# DIOT_Connectors.net
KiCad netlist of a schematic drawn in Altium Designer
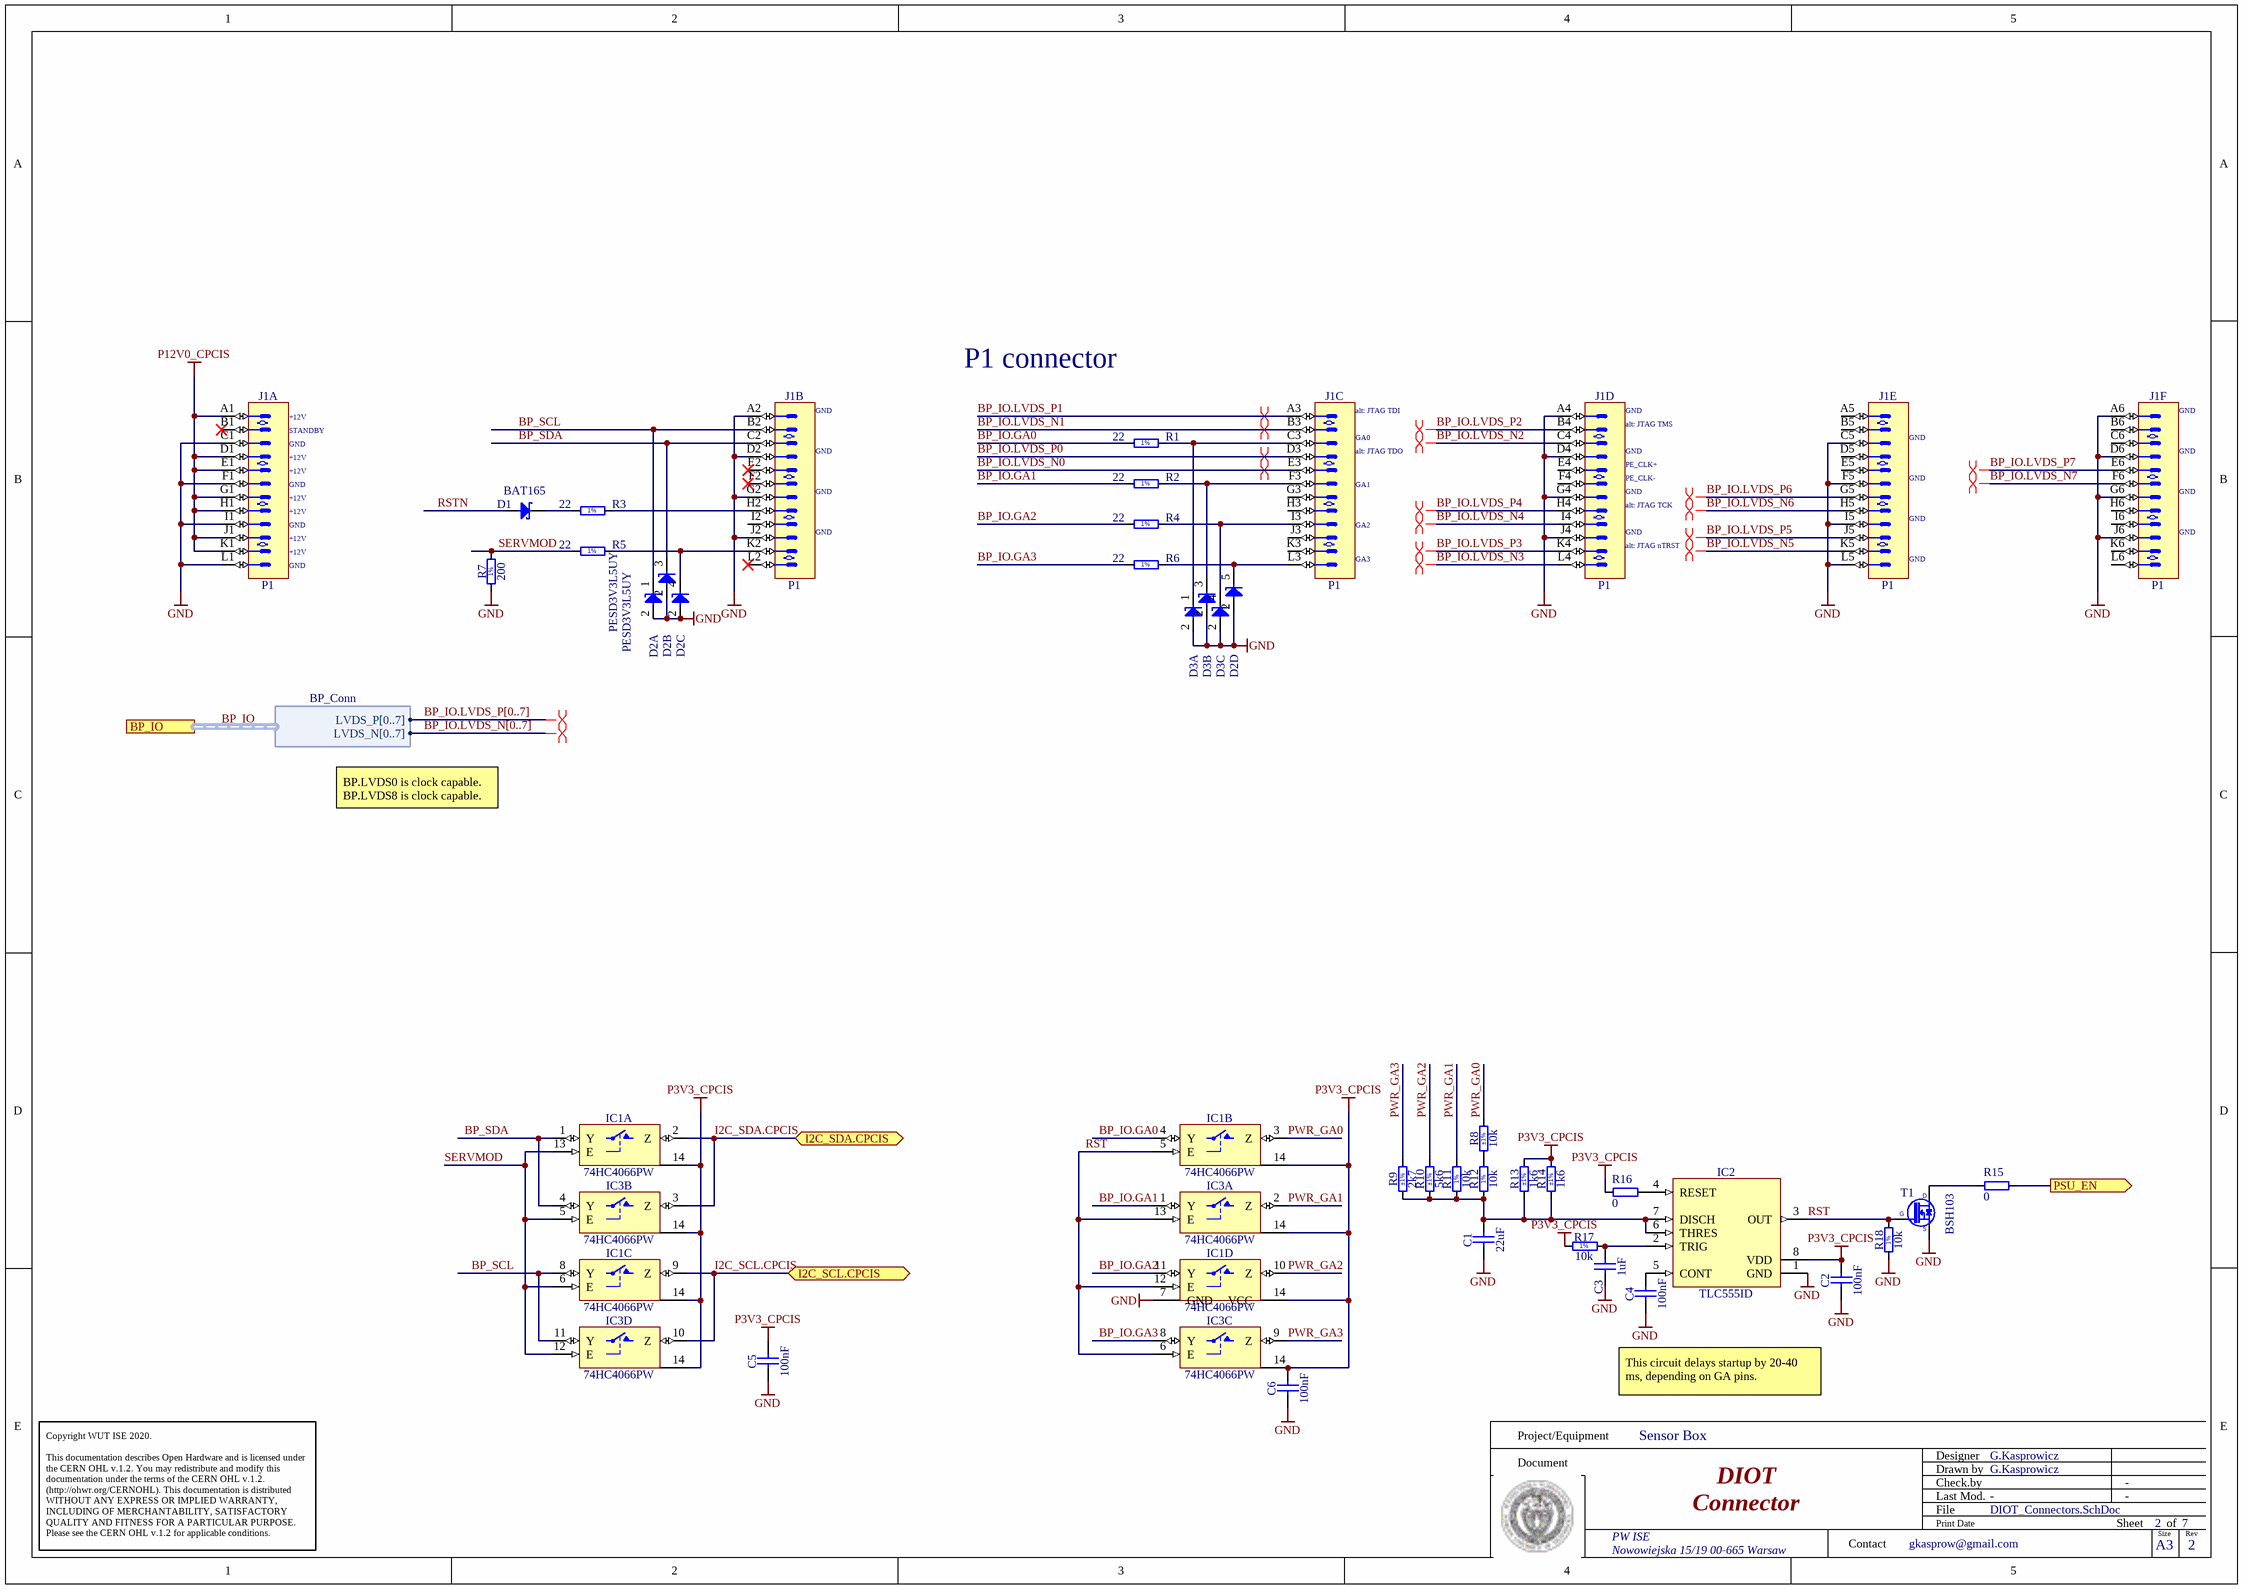
[diagram p0: DIOT_Connectors.SchDoc]

(export (version "E")
  (design (tool "Eeschema 10.0.6"))
  (components
    (comp (ref "C1")
      (value "22uF")
      (footprint "CAPC1608X90N")
      (description "Non-polarised capacitor")
      (fields
        (field (name "MANUFACTURER") "GENERIC")
        (field (name "PART NUMBER") "CC0603_22UF_6.3V_20%_X5R")
        (field (name "AUTHOR") "CERN DEM JLC")
      )
      (libsource (lib "Capacitors") (part "Capacitor - non polarized"))
    )
    (comp (ref "C2")
      (value "100nF")
      (footprint "CAPC1005X55N")
      (description "Non-polarised capacitor")
      (fields
        (field (name "PART NUMBER") "CC0402_100NF_16V_10%_X5R")
        (field (name "VOLTAGE") "16V")
        (field (name "AUTHOR") "CERN DEM JLC")
      )
      (libsource (lib "Capacitors") (part "Capacitor - non polarized"))
    )
    (comp (ref "C3")
      (value "1uF")
      (footprint "CAPC1005X55N")
      (description "Non-polarised capacitor")
      (fields
        (field (name "PART NUMBER") "CC0402_1UF_16V_10%_X5R")
        (field (name "VOLTAGE") "16V")
        (field (name "AUTHOR") "CERN DEM JLC")
      )
      (libsource (lib "Capacitors") (part "Capacitor - non polarized"))
    )
    (comp (ref "C4")
      (value "100nF")
      (footprint "CAPC1005X55N")
      (description "Non-polarised capacitor")
      (fields
        (field (name "PART NUMBER") "CC0402_100NF_16V_10%_X5R")
        (field (name "VOLTAGE") "16V")
        (field (name "AUTHOR") "CERN DEM JLC")
      )
      (libsource (lib "Capacitors") (part "Capacitor - non polarized"))
    )
    (comp (ref "C5")
      (value "100nF")
      (footprint "CAPC1005X55N")
      (description "Non-polarised capacitor")
      (fields
        (field (name "PART NUMBER") "CC0402_100NF_16V_10%_X5R")
        (field (name "VOLTAGE") "16V")
        (field (name "AUTHOR") "CERN DEM JLC")
      )
      (libsource (lib "Capacitors") (part "Capacitor - non polarized"))
    )
    (comp (ref "C6")
      (value "100nF")
      (footprint "CAPC1005X55N")
      (description "Non-polarised capacitor")
      (fields
        (field (name "PART NUMBER") "CC0402_100NF_16V_10%_X5R")
        (field (name "VOLTAGE") "16V")
        (field (name "AUTHOR") "CERN DEM JLC")
      )
      (libsource (lib "Capacitors") (part "Capacitor - non polarized"))
    )
    (comp (ref "D1")
      (value "BAT165")
      (footprint "SOD2512X110N")
      (description "Schottky Diode")
      (fields
        (field (name "MANUFACTURER") "INFINEON")
        (field (name "VOLTAGE") "40V")
        (field (name "AUTHOR") "CERN DEM JLC")
      )
      (libsource (lib "ICs And Semiconductors") (part "Diode Schottky"))
    )
    (comp (ref "D2")
      (value "PESD3V3L5UY")
      (footprint "SOT65P210X110-6N")
      (description "Fivefold ESD Protection Diode Arrays")
      (fields
        (field (name "VOLTAGE") "3.3V")
        (field (name "POWER") "200W")
        (field (name "AUTHOR") "CERN DEM WB")
      )
      (libsource (lib "ICs And Semiconductors") (part "PESD Array 5diodes 6pins Common anode2"))
    )
    (comp (ref "D3")
      (value "PESD3V3L5UY")
      (footprint "SOT65P210X110-6N")
      (description "Fivefold ESD Protection Diode Arrays")
      (fields
        (field (name "VOLTAGE") "3.3V")
        (field (name "POWER") "200W")
        (field (name "AUTHOR") "CERN DEM WB")
      )
      (libsource (lib "ICs And Semiconductors") (part "PESD Array 5diodes 6pins Common anode2"))
    )
    (comp (ref "IC1")
      (value "74HC4066PW")
      (footprint "SOP65P640X110-14N")
      (fields (field (name "MANUFACTURER") "NXP SEMICONDUCTORS") (field (name "AUTHOR") "CERN DEM JLC"))
      (libsource (lib "ICs And Semiconductors") (part "4066"))
    )
    (comp (ref "IC2")
      (value "TLC555ID")
      (footprint "SOIC127P600X175-8N")
      (description "LinCMOS Timer")
      (fields (field (name "MANUFACTURER") "TEXAS INSTRUMENTS") (field (name "AUTHOR") "CERN DEM JMW"))
      (libsource (lib "ICs And Semiconductors") (part "TLC555"))
    )
    (comp (ref "IC3")
      (value "74HC4066PW")
      (footprint "SOP65P640X110-14N")
      (fields (field (name "MANUFACTURER") "NXP SEMICONDUCTORS") (field (name "AUTHOR") "CERN DEM JLC"))
      (libsource (lib "ICs And Semiconductors") (part "4066"))
    )
    (comp (ref "J1")
      (value "P1")
      (footprint "AMPHENOL_10052825-101LF")
      (description "72 Contacts Header, 6 Columns, 4 Pairs per Column")
      (fields
        (field (name "PART NUMBER") "AMPHENOL_10052825-101LF")
        (field (name "MANUFACTURER") "AMPHENOL")
        (field (name "AUTHOR") "CERN DEM MR")
      )
      (libsource (lib "Connectors") (part "AMPHENOL_10052825-101LF"))
    )
    (comp (ref "R1")
      (value "22")
      (footprint "RESC1005X40N")
      (description "Resistor - 1%")
      (fields
        (field (name "PART NUMBER") "R0402_22R_1%_0.0625W_100PPM")
        (field (name "POWER") "0.0625W")
        (field (name "AUTHOR") "CERN DEM JLC")
      )
      (libsource (lib "Resistors") (part "Resistor - 1%"))
    )
    (comp (ref "R2")
      (value "22")
      (footprint "RESC1005X40N")
      (description "Resistor - 1%")
      (fields
        (field (name "PART NUMBER") "R0402_22R_1%_0.0625W_100PPM")
        (field (name "POWER") "0.0625W")
        (field (name "AUTHOR") "CERN DEM JLC")
      )
      (libsource (lib "Resistors") (part "Resistor - 1%"))
    )
    (comp (ref "R3")
      (value "22")
      (footprint "RESC1005X40N")
      (description "Resistor - 1%")
      (fields
        (field (name "PART NUMBER") "R0402_22R_1%_0.0625W_100PPM")
        (field (name "POWER") "0.0625W")
        (field (name "AUTHOR") "CERN DEM JLC")
      )
      (libsource (lib "Resistors") (part "Resistor - 1%"))
    )
    (comp (ref "R4")
      (value "22")
      (footprint "RESC1005X40N")
      (description "Resistor - 1%")
      (fields
        (field (name "PART NUMBER") "R0402_22R_1%_0.0625W_100PPM")
        (field (name "POWER") "0.0625W")
        (field (name "AUTHOR") "CERN DEM JLC")
      )
      (libsource (lib "Resistors") (part "Resistor - 1%"))
    )
    (comp (ref "R5")
      (value "22")
      (footprint "RESC1005X40N")
      (description "Resistor - 1%")
      (fields
        (field (name "PART NUMBER") "R0402_22R_1%_0.0625W_100PPM")
        (field (name "POWER") "0.0625W")
        (field (name "AUTHOR") "CERN DEM JLC")
      )
      (libsource (lib "Resistors") (part "Resistor - 1%"))
    )
    (comp (ref "R6")
      (value "22")
      (footprint "RESC1005X40N")
      (description "Resistor - 1%")
      (fields
        (field (name "PART NUMBER") "R0402_22R_1%_0.0625W_100PPM")
        (field (name "POWER") "0.0625W")
        (field (name "AUTHOR") "CERN DEM JLC")
      )
      (libsource (lib "Resistors") (part "Resistor - 1%"))
    )
    (comp (ref "R7")
      (value "200")
      (footprint "RESC1005X40N")
      (description "Resistor - 1%")
      (fields
        (field (name "PART NUMBER") "R0402_200R_1%_0.0625W_100PPM")
        (field (name "POWER") "0.0625W")
        (field (name "AUTHOR") "CERN DEM JLC")
      )
      (libsource (lib "Resistors") (part "Resistor - 1%"))
    )
    (comp (ref "R8")
      (value "10k")
      (footprint "RESC1005X40N")
      (description "Resistor - 1%")
      (fields
        (field (name "PART NUMBER") "R0402_10K_1%_0.0625W_100PPM")
        (field (name "POWER") "0.0625W")
        (field (name "TOLERANCE") "±1%")
        (field (name "AUTHOR") "CERN DEM JLC")
      )
      (libsource (lib "Resistors") (part "Resistor - 1%"))
    )
    (comp (ref "R9")
      (value "2k7")
      (footprint "RESC1608X55N")
      (description "Resistor - 1%")
      (fields
        (field (name "PART NUMBER") "R0603_2K7_1%_0.1W_100PPM")
        (field (name "POWER") "0.1W")
        (field (name "TOLERANCE") "±1%")
        (field (name "AUTHOR") "CERN DEM JLC")
      )
      (libsource (lib "Resistors") (part "Resistor - 1%"))
    )
    (comp (ref "R10")
      (value "5k6")
      (footprint "RESC1005X40N")
      (description "Resistor - 1%")
      (fields
        (field (name "PART NUMBER") "R0402_5K6_1%_0.0625W_100PPM")
        (field (name "POWER") "0.0625W")
        (field (name "TOLERANCE") "±1%")
        (field (name "AUTHOR") "CERN DEM JLC")
      )
      (libsource (lib "Resistors") (part "Resistor - 1%"))
    )
    (comp (ref "R11")
      (value "10k")
      (footprint "RESC1005X40N")
      (description "Resistor - 1%")
      (fields
        (field (name "PART NUMBER") "R0402_1K_1%_0.0625W_100PPM")
        (field (name "POWER") "0.0625W")
        (field (name "AUTHOR") "CERN DEM JLC")
      )
      (libsource (lib "Resistors") (part "Resistor - 1%"))
    )
    (comp (ref "R12")
      (value "10k")
      (footprint "RESC1005X40N")
      (description "Resistor - 1%")
      (fields
        (field (name "PART NUMBER") "R0402_1K_1%_0.0625W_100PPM")
        (field (name "POWER") "0.0625W")
        (field (name "AUTHOR") "CERN DEM JLC")
      )
      (libsource (lib "Resistors") (part "Resistor - 1%"))
    )
    (comp (ref "R13")
      (value "1k6")
      (footprint "RESC1005X40N")
      (description "Resistor - 1%")
      (fields
        (field (name "PART NUMBER") "R0402_1K6_1%_0.0625W_100PPM")
        (field (name "POWER") "0.0625W")
        (field (name "TOLERANCE") "±1%")
        (field (name "AUTHOR") "CERN DEM JLC")
      )
      (libsource (lib "Resistors") (part "Resistor - 1%"))
    )
    (comp (ref "R14")
      (value "1k6")
      (footprint "RESC1005X40N")
      (description "Resistor - 1%")
      (fields
        (field (name "PART NUMBER") "R0402_1K6_1%_0.0625W_100PPM")
        (field (name "POWER") "0.0625W")
        (field (name "TOLERANCE") "±1%")
        (field (name "AUTHOR") "CERN DEM JLC")
      )
      (libsource (lib "Resistors") (part "Resistor - 1%"))
    )
    (comp (ref "R15")
      (value "0")
      (footprint "RESC1005X40N")
      (description "Resistor")
      (fields
        (field (name "PART NUMBER") "R0402_0R_JUMPER")
        (field (name "MANUFACTURER") "GENERIC")
        (field (name "AUTHOR") "CERN DEM JLC")
      )
      (libsource (lib "Resistors") (part "Resistor"))
    )
    (comp (ref "R16")
      (value "0")
      (footprint "RESC1005X40N")
      (description "Resistor")
      (fields
        (field (name "PART NUMBER") "R0402_0R_JUMPER")
        (field (name "MANUFACTURER") "GENERIC")
        (field (name "AUTHOR") "CERN DEM JLC")
      )
      (libsource (lib "Resistors") (part "Resistor"))
    )
    (comp (ref "R17")
      (value "10k")
      (footprint "RESC1005X40N")
      (description "Resistor - 1%")
      (fields
        (field (name "PART NUMBER") "R0402_10K_1%_0.0625W_100PPM")
        (field (name "POWER") "0.0625W")
        (field (name "AUTHOR") "CERN DEM JLC")
      )
      (libsource (lib "Resistors") (part "Resistor - 1%"))
    )
    (comp (ref "R18")
      (value "10k")
      (footprint "RESC1005X40N")
      (description "Resistor - 1%")
      (fields
        (field (name "PART NUMBER") "R0402_10K_1%_0.0625W_100PPM")
        (field (name "POWER") "0.0625W")
        (field (name "AUTHOR") "CERN DEM JLC")
      )
      (libsource (lib "Resistors") (part "Resistor - 1%"))
    )
    (comp (ref "T1")
      (value "BSH103")
      (footprint "SOT95P230X110-3N")
      (description "N-CHANNEL MOSFET WITH DIODE")
      (fields (field (name "MANUFACTURER") "NEXPERIA") (field (name "AUTHOR") "CERN DEM JLC"))
      (libsource (lib "ICs And Semiconductors") (part "N-MOSFET-D 1G 2S 3D"))
    )
  )
  (nets
    (net (code "2") (name "/BP_IO.GA0") (class "Default")
      (node (ref "IC1") (pin "4") (pinfunction "Y_4") (pintype "bidirectional"))
      (node (ref "R1") (pin "1") (pinfunction "1_1") (pintype "passive"))
    )
    (net (code "3") (name "/BP_IO.GA1") (class "Default")
      (node (ref "IC3") (pin "1") (pinfunction "Y_1") (pintype "bidirectional"))
      (node (ref "R2") (pin "1") (pinfunction "1_1") (pintype "passive"))
    )
    (net (code "4") (name "/BP_IO.GA2") (class "Default")
      (node (ref "IC1") (pin "11") (pinfunction "Y_11") (pintype "bidirectional"))
      (node (ref "R4") (pin "1") (pinfunction "1_1") (pintype "passive"))
    )
    (net (code "5") (name "/BP_IO.GA3") (class "Default")
      (node (ref "IC3") (pin "8") (pinfunction "Y_8") (pintype "bidirectional"))
      (node (ref "R6") (pin "1") (pinfunction "1_1") (pintype "passive"))
    )
    (net (code "6") (name "/BP_IO.LVDS_N0") (class "Default")
      (node (ref "J1") (pin "E3") (pinfunction "E3_E3") (pintype "bidirectional"))
    )
    (net (code "7") (name "/BP_IO.LVDS_N1") (class "Default")
      (node (ref "J1") (pin "B3") (pinfunction "B3_B3") (pintype "bidirectional"))
    )
    (net (code "8") (name "/BP_IO.LVDS_N2") (class "Default")
      (node (ref "J1") (pin "C4") (pinfunction "C4_C4") (pintype "bidirectional"))
    )
    (net (code "9") (name "/BP_IO.LVDS_N3") (class "Default")
      (node (ref "J1") (pin "L4") (pinfunction "L4_L4") (pintype "bidirectional"))
    )
    (net (code "10") (name "/BP_IO.LVDS_N4") (class "Default")
      (node (ref "J1") (pin "I4") (pinfunction "I4_I4") (pintype "bidirectional"))
    )
    (net (code "11") (name "/BP_IO.LVDS_N5") (class "Default")
      (node (ref "J1") (pin "K5") (pinfunction "K5_K5") (pintype "bidirectional"))
    )
    (net (code "12") (name "/BP_IO.LVDS_N6") (class "Default")
      (node (ref "J1") (pin "H5") (pinfunction "H5_H5") (pintype "bidirectional"))
    )
    (net (code "13") (name "/BP_IO.LVDS_N7") (class "Default")
      (node (ref "J1") (pin "F6") (pinfunction "F6_F6") (pintype "bidirectional"))
    )
    (net (code "15") (name "/BP_IO.LVDS_P0") (class "Default")
      (node (ref "J1") (pin "D3") (pinfunction "D3_D3") (pintype "bidirectional"))
    )
    (net (code "16") (name "/BP_IO.LVDS_P1") (class "Default")
      (node (ref "J1") (pin "A3") (pinfunction "A3_A3") (pintype "bidirectional"))
    )
    (net (code "17") (name "/BP_IO.LVDS_P2") (class "Default")
      (node (ref "J1") (pin "B4") (pinfunction "B4_B4") (pintype "bidirectional"))
    )
    (net (code "18") (name "/BP_IO.LVDS_P3") (class "Default")
      (node (ref "J1") (pin "K4") (pinfunction "K4_K4") (pintype "bidirectional"))
    )
    (net (code "19") (name "/BP_IO.LVDS_P4") (class "Default")
      (node (ref "J1") (pin "H4") (pinfunction "H4_H4") (pintype "bidirectional"))
    )
    (net (code "20") (name "/BP_IO.LVDS_P5") (class "Default")
      (node (ref "J1") (pin "J5") (pinfunction "J5_J5") (pintype "bidirectional"))
    )
    (net (code "21") (name "/BP_IO.LVDS_P6") (class "Default")
      (node (ref "J1") (pin "G5") (pinfunction "G5_G5") (pintype "bidirectional"))
    )
    (net (code "22") (name "/BP_IO.LVDS_P7") (class "Default")
      (node (ref "J1") (pin "E6") (pinfunction "E6_E6") (pintype "bidirectional"))
    )
    (net (code "25") (name "/BP_SCL") (class "Default")
      (node (ref "D2") (pin "1") (pinfunction "C_1") (pintype "passive"))
      (node (ref "IC1") (pin "8") (pinfunction "Y_8") (pintype "bidirectional"))
      (node (ref "IC3") (pin "11") (pinfunction "Y_11") (pintype "bidirectional"))
      (node (ref "J1") (pin "B2") (pinfunction "B2_B2") (pintype "bidirectional"))
    )
    (net (code "26") (name "/BP_SDA") (class "Default")
      (node (ref "D2") (pin "3") (pinfunction "C_3") (pintype "passive"))
      (node (ref "IC1") (pin "1") (pinfunction "Y_1") (pintype "bidirectional"))
      (node (ref "IC3") (pin "4") (pinfunction "Y_4") (pintype "bidirectional"))
      (node (ref "J1") (pin "C2") (pinfunction "C2_C2") (pintype "bidirectional"))
    )
    (net (code "27") (name "/I2C_SCL.CPCIS") (class "Default")
      (node (ref "IC1") (pin "9") (pinfunction "Z_9") (pintype "bidirectional"))
      (node (ref "IC3") (pin "10") (pinfunction "Z_10") (pintype "bidirectional"))
    )
    (net (code "28") (name "/I2C_SDA.CPCIS") (class "Default")
      (node (ref "IC1") (pin "2") (pinfunction "Z_2") (pintype "bidirectional"))
      (node (ref "IC3") (pin "3") (pinfunction "Z_3") (pintype "bidirectional"))
    )
    (net (code "29") (name "/PSU_EN") (class "Default")
      (node (ref "R15") (pin "1") (pinfunction "1_1") (pintype "passive"))
    )
    (net (code "30") (name "/PWR_GA0") (class "Default")
      (node (ref "IC1") (pin "3") (pinfunction "Z_3") (pintype "bidirectional"))
      (node (ref "R8") (pin "2") (pinfunction "2_2") (pintype "passive"))
    )
    (net (code "31") (name "/PWR_GA1") (class "Default")
      (node (ref "IC3") (pin "2") (pinfunction "Z_2") (pintype "bidirectional"))
      (node (ref "R11") (pin "2") (pinfunction "2_2") (pintype "passive"))
    )
    (net (code "32") (name "/PWR_GA2") (class "Default")
      (node (ref "IC1") (pin "10") (pinfunction "Z_10") (pintype "bidirectional"))
      (node (ref "R10") (pin "2") (pinfunction "2_2") (pintype "passive"))
    )
    (net (code "33") (name "/PWR_GA3") (class "Default")
      (node (ref "IC3") (pin "9") (pinfunction "Z_9") (pintype "bidirectional"))
      (node (ref "R9") (pin "2") (pinfunction "2_2") (pintype "passive"))
    )
    (net (code "34") (name "/RST") (class "Default")
      (node (ref "IC1") (pin "12") (pinfunction "E_12") (pintype "input"))
      (node (ref "IC1") (pin "5") (pinfunction "E_5") (pintype "input"))
      (node (ref "IC2") (pin "3") (pinfunction "OUT_3") (pintype "output"))
      (node (ref "IC3") (pin "13") (pinfunction "E_13") (pintype "input"))
      (node (ref "IC3") (pin "6") (pinfunction "E_6") (pintype "input"))
      (node (ref "R18") (pin "2") (pinfunction "2_2") (pintype "passive"))
      (node (ref "T1") (pin "1") (pinfunction "G_1") (pintype "passive"))
    )
    (net (code "35") (name "/RSTN") (class "Default")
      (node (ref "D1") (pin "2") (pinfunction "A_2") (pintype "passive"))
    )
    (net (code "36") (name "/SERVMOD") (class "Default")
      (node (ref "IC1") (pin "13") (pinfunction "E_13") (pintype "input"))
      (node (ref "IC1") (pin "6") (pinfunction "E_6") (pintype "input"))
      (node (ref "IC3") (pin "12") (pinfunction "E_12") (pintype "input"))
      (node (ref "IC3") (pin "5") (pinfunction "E_5") (pintype "input"))
      (node (ref "R5") (pin "1") (pinfunction "1_1") (pintype "passive"))
      (node (ref "R7") (pin "2") (pinfunction "2_2") (pintype "passive"))
    )
    (net (code "37") (name "GND") (class "Default")
      (node (ref "C1") (pin "1") (pinfunction "1_1") (pintype "passive"))
      (node (ref "C2") (pin "1") (pinfunction "1_1") (pintype "passive"))
      (node (ref "C3") (pin "1") (pinfunction "1_1") (pintype "passive"))
      (node (ref "C4") (pin "1") (pinfunction "1_1") (pintype "passive"))
      (node (ref "C5") (pin "1") (pinfunction "1_1") (pintype "passive"))
      (node (ref "C6") (pin "1") (pinfunction "1_1") (pintype "passive"))
      (node (ref "D2") (pin "2") (pinfunction "A_2") (pintype "passive"))
      (node (ref "D3") (pin "2") (pinfunction "A_2") (pintype "passive"))
      (node (ref "IC1") (pin "7") (pinfunction "GND_7") (pintype "power_in"))
      (node (ref "IC2") (pin "1") (pinfunction "GND_1") (pintype "power_in"))
      (node (ref "IC3") (pin "7") (pinfunction "GND_7") (pintype "power_in"))
      (node (ref "J1") (pin "A2") (pinfunction "A2_A2") (pintype "bidirectional"))
      (node (ref "J1") (pin "A4") (pinfunction "A4_A4") (pintype "bidirectional"))
      (node (ref "J1") (pin "A6") (pinfunction "A6_A6") (pintype "bidirectional"))
      (node (ref "J1") (pin "C1") (pinfunction "C1_C1") (pintype "bidirectional"))
      (node (ref "J1") (pin "C5") (pinfunction "C5_C5") (pintype "bidirectional"))
      (node (ref "J1") (pin "D2") (pinfunction "D2_D2") (pintype "bidirectional"))
      (node (ref "J1") (pin "D4") (pinfunction "D4_D4") (pintype "bidirectional"))
      (node (ref "J1") (pin "D6") (pinfunction "D6_D6") (pintype "bidirectional"))
      (node (ref "J1") (pin "F1") (pinfunction "F1_F1") (pintype "bidirectional"))
      (node (ref "J1") (pin "F5") (pinfunction "F5_F5") (pintype "bidirectional"))
      (node (ref "J1") (pin "G2") (pinfunction "G2_G2") (pintype "bidirectional"))
      (node (ref "J1") (pin "G4") (pinfunction "G4_G4") (pintype "bidirectional"))
      (node (ref "J1") (pin "G6") (pinfunction "G6_G6") (pintype "bidirectional"))
      (node (ref "J1") (pin "I1") (pinfunction "I1_I1") (pintype "bidirectional"))
      (node (ref "J1") (pin "I5") (pinfunction "I5_I5") (pintype "bidirectional"))
      (node (ref "J1") (pin "J2") (pinfunction "J2_J2") (pintype "bidirectional"))
      (node (ref "J1") (pin "J4") (pinfunction "J4_J4") (pintype "bidirectional"))
      (node (ref "J1") (pin "J6") (pinfunction "J6_J6") (pintype "bidirectional"))
      (node (ref "J1") (pin "L1") (pinfunction "L1_L1") (pintype "bidirectional"))
      (node (ref "J1") (pin "L5") (pinfunction "L5_L5") (pintype "bidirectional"))
      (node (ref "R18") (pin "1") (pinfunction "1_1") (pintype "passive"))
      (node (ref "R7") (pin "1") (pinfunction "1_1") (pintype "passive"))
      (node (ref "T1") (pin "2") (pinfunction "S_2") (pintype "passive"))
    )
    (net (code "38") (name "Net-(D1-C)") (class "Default")
      (node (ref "D1") (pin "1") (pinfunction "C_1") (pintype "passive"))
      (node (ref "R3") (pin "1") (pinfunction "1_1") (pintype "passive"))
    )
    (net (code "39") (name "Net-(D2C-C)") (class "Default")
      (node (ref "D2") (pin "4") (pinfunction "C_4") (pintype "passive"))
      (node (ref "J1") (pin "K2") (pinfunction "K2_K2") (pintype "bidirectional"))
      (node (ref "R5") (pin "2") (pinfunction "2_2") (pintype "passive"))
    )
    (net (code "40") (name "Net-(D2D-C)") (class "Default")
      (node (ref "D2") (pin "5") (pinfunction "C_5") (pintype "passive"))
      (node (ref "J1") (pin "L3") (pinfunction "L3_L3") (pintype "bidirectional"))
      (node (ref "R6") (pin "2") (pinfunction "2_2") (pintype "passive"))
    )
    (net (code "41") (name "Net-(D3A-C)") (class "Default")
      (node (ref "D3") (pin "1") (pinfunction "C_1") (pintype "passive"))
      (node (ref "J1") (pin "C3") (pinfunction "C3_C3") (pintype "bidirectional"))
      (node (ref "R1") (pin "2") (pinfunction "2_2") (pintype "passive"))
    )
    (net (code "42") (name "Net-(D3B-C)") (class "Default")
      (node (ref "D3") (pin "3") (pinfunction "C_3") (pintype "passive"))
      (node (ref "J1") (pin "F3") (pinfunction "F3_F3") (pintype "bidirectional"))
      (node (ref "R2") (pin "2") (pinfunction "2_2") (pintype "passive"))
    )
    (net (code "43") (name "Net-(D3C-C)") (class "Default")
      (node (ref "D3") (pin "4") (pinfunction "C_4") (pintype "passive"))
      (node (ref "J1") (pin "I3") (pinfunction "I3_I3") (pintype "bidirectional"))
      (node (ref "R4") (pin "2") (pinfunction "2_2") (pintype "passive"))
    )
    (net (code "44") (name "Net-(IC2-CONT)") (class "Default")
      (node (ref "C4") (pin "2") (pinfunction "2_2") (pintype "passive"))
      (node (ref "IC2") (pin "5") (pinfunction "CONT_5") (pintype "input"))
    )
    (net (code "45") (name "Net-(IC2-DISCH)") (class "Default")
      (node (ref "C1") (pin "2") (pinfunction "2_2") (pintype "passive"))
      (node (ref "IC2") (pin "6") (pinfunction "THRES_6") (pintype "input"))
      (node (ref "IC2") (pin "7") (pinfunction "DISCH_7") (pintype "input"))
      (node (ref "R10") (pin "1") (pinfunction "1_1") (pintype "passive"))
      (node (ref "R11") (pin "1") (pinfunction "1_1") (pintype "passive"))
      (node (ref "R12") (pin "1") (pinfunction "1_1") (pintype "passive"))
      (node (ref "R13") (pin "1") (pinfunction "1_1") (pintype "passive"))
      (node (ref "R14") (pin "1") (pinfunction "1_1") (pintype "passive"))
      (node (ref "R9") (pin "1") (pinfunction "1_1") (pintype "passive"))
    )
    (net (code "46") (name "Net-(IC2-RESET)") (class "Default")
      (node (ref "IC2") (pin "4") (pinfunction "RESET_4") (pintype "input"))
      (node (ref "R16") (pin "1") (pinfunction "1_1") (pintype "passive"))
    )
    (net (code "47") (name "Net-(IC2-TRIG)") (class "Default")
      (node (ref "C3") (pin "2") (pinfunction "2_2") (pintype "passive"))
      (node (ref "IC2") (pin "2") (pinfunction "TRIG_2") (pintype "input"))
      (node (ref "R17") (pin "2") (pinfunction "2_2") (pintype "passive"))
    )
    (net (code "48") (name "Net-(J1-PadH2)") (class "Default")
      (node (ref "J1") (pin "H2") (pinfunction "H2_H2") (pintype "bidirectional"))
      (node (ref "R3") (pin "2") (pinfunction "2_2") (pintype "passive"))
    )
    (net (code "49") (name "Net-(R12-Pad2)") (class "Default")
      (node (ref "R12") (pin "2") (pinfunction "2_2") (pintype "passive"))
      (node (ref "R8") (pin "1") (pinfunction "1_1") (pintype "passive"))
    )
    (net (code "50") (name "Net-(T1-D)") (class "Default")
      (node (ref "R15") (pin "2") (pinfunction "2_2") (pintype "passive"))
      (node (ref "T1") (pin "3") (pinfunction "D_3") (pintype "passive"))
    )
    (net (code "51") (name "P3V3_CPCIS") (class "Default")
      (node (ref "C2") (pin "2") (pinfunction "2_2") (pintype "passive"))
      (node (ref "C5") (pin "2") (pinfunction "2_2") (pintype "passive"))
      (node (ref "C6") (pin "2") (pinfunction "2_2") (pintype "passive"))
      (node (ref "IC1") (pin "14") (pinfunction "VCC_14") (pintype "power_in"))
      (node (ref "IC2") (pin "8") (pinfunction "VDD_8") (pintype "power_in"))
      (node (ref "IC3") (pin "14") (pinfunction "VCC_14") (pintype "power_in"))
      (node (ref "R13") (pin "2") (pinfunction "2_2") (pintype "passive"))
      (node (ref "R14") (pin "2") (pinfunction "2_2") (pintype "passive"))
      (node (ref "R16") (pin "2") (pinfunction "2_2") (pintype "passive"))
      (node (ref "R17") (pin "1") (pinfunction "1_1") (pintype "passive"))
    )
    (net (code "52") (name "P12V0_CPCIS") (class "Default")
      (node (ref "J1") (pin "A1") (pinfunction "A1_A1") (pintype "bidirectional"))
      (node (ref "J1") (pin "D1") (pinfunction "D1_D1") (pintype "bidirectional"))
      (node (ref "J1") (pin "E1") (pinfunction "E1_E1") (pintype "bidirectional"))
      (node (ref "J1") (pin "G1") (pinfunction "G1_G1") (pintype "bidirectional"))
      (node (ref "J1") (pin "H1") (pinfunction "H1_H1") (pintype "bidirectional"))
      (node (ref "J1") (pin "J1") (pinfunction "J1_J1") (pintype "bidirectional"))
      (node (ref "J1") (pin "K1") (pinfunction "K1_K1") (pintype "bidirectional"))
    )
    (net (code "53") (name "unconnected-(J1-PadA5)") (class "Default")
      (node (ref "J1") (pin "A5") (pinfunction "A5_A5") (pintype "bidirectional"))
    )
    (net (code "54") (name "unconnected-(J1-PadB1)") (class "Default")
      (node (ref "J1") (pin "B1") (pinfunction "B1_B1") (pintype "bidirectional+no_connect"))
    )
    (net (code "55") (name "unconnected-(J1-PadB5)") (class "Default")
      (node (ref "J1") (pin "B5") (pinfunction "B5_B5") (pintype "bidirectional"))
    )
    (net (code "56") (name "unconnected-(J1-PadB6)") (class "Default")
      (node (ref "J1") (pin "B6") (pinfunction "B6_B6") (pintype "bidirectional"))
    )
    (net (code "57") (name "unconnected-(J1-PadC6)") (class "Default")
      (node (ref "J1") (pin "C6") (pinfunction "C6_C6") (pintype "bidirectional"))
    )
    (net (code "58") (name "unconnected-(J1-PadD5)") (class "Default")
      (node (ref "J1") (pin "D5") (pinfunction "D5_D5") (pintype "bidirectional"))
    )
    (net (code "59") (name "unconnected-(J1-PadE2)") (class "Default")
      (node (ref "J1") (pin "E2") (pinfunction "E2_E2") (pintype "bidirectional+no_connect"))
    )
    (net (code "60") (name "unconnected-(J1-PadE4)") (class "Default")
      (node (ref "J1") (pin "E4") (pinfunction "E4_E4") (pintype "bidirectional"))
    )
    (net (code "61") (name "unconnected-(J1-PadE5)") (class "Default")
      (node (ref "J1") (pin "E5") (pinfunction "E5_E5") (pintype "bidirectional"))
    )
    (net (code "62") (name "unconnected-(J1-PadF2)") (class "Default")
      (node (ref "J1") (pin "F2") (pinfunction "F2_F2") (pintype "bidirectional+no_connect"))
    )
    (net (code "63") (name "unconnected-(J1-PadF4)") (class "Default")
      (node (ref "J1") (pin "F4") (pinfunction "F4_F4") (pintype "bidirectional"))
    )
    (net (code "64") (name "unconnected-(J1-PadG3)") (class "Default")
      (node (ref "J1") (pin "G3") (pinfunction "G3_G3") (pintype "bidirectional"))
    )
    (net (code "65") (name "unconnected-(J1-PadH3)") (class "Default")
      (node (ref "J1") (pin "H3") (pinfunction "H3_H3") (pintype "bidirectional"))
    )
    (net (code "66") (name "unconnected-(J1-PadH6)") (class "Default")
      (node (ref "J1") (pin "H6") (pinfunction "H6_H6") (pintype "bidirectional"))
    )
    (net (code "67") (name "unconnected-(J1-PadI2)") (class "Default")
      (node (ref "J1") (pin "I2") (pinfunction "I2_I2") (pintype "bidirectional"))
    )
    (net (code "68") (name "unconnected-(J1-PadI6)") (class "Default")
      (node (ref "J1") (pin "I6") (pinfunction "I6_I6") (pintype "bidirectional"))
    )
    (net (code "69") (name "unconnected-(J1-PadJ3)") (class "Default")
      (node (ref "J1") (pin "J3") (pinfunction "J3_J3") (pintype "bidirectional"))
    )
    (net (code "70") (name "unconnected-(J1-PadK3)") (class "Default")
      (node (ref "J1") (pin "K3") (pinfunction "K3_K3") (pintype "bidirectional"))
    )
    (net (code "71") (name "unconnected-(J1-PadK6)") (class "Default")
      (node (ref "J1") (pin "K6") (pinfunction "K6_K6") (pintype "bidirectional"))
    )
    (net (code "72") (name "unconnected-(J1-PadL2)") (class "Default")
      (node (ref "J1") (pin "L2") (pinfunction "L2_L2") (pintype "bidirectional+no_connect"))
    )
    (net (code "73") (name "unconnected-(J1-PadL6)") (class "Default")
      (node (ref "J1") (pin "L6") (pinfunction "L6_L6") (pintype "bidirectional"))
    )
  )
)
